# Sheet3_Power.net
KiCad netlist of a schematic drawn in Altium Designer
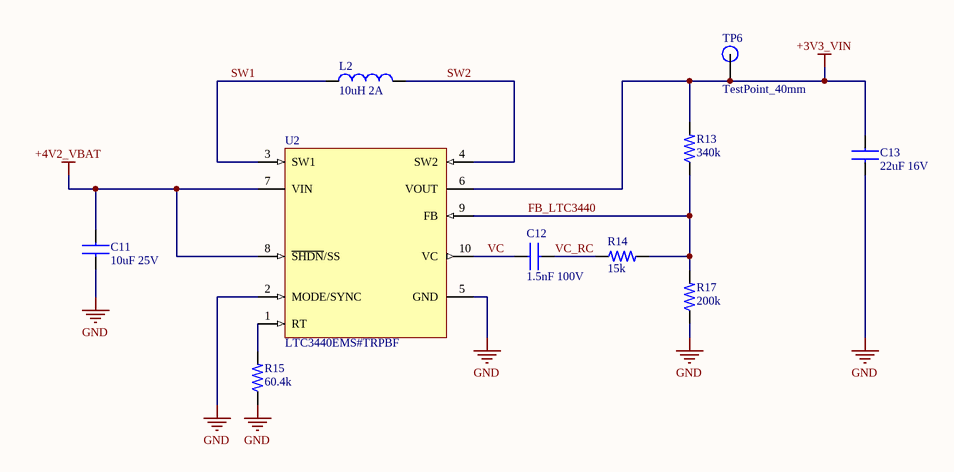
[diagram p0: Sheet3_Power.SchDoc]

(export (version "E")
  (design (tool "Eeschema 10.0.6"))
  (components
    (comp (ref "C11")
      (value "10uF 25V")
      (footprint "CAP_0805_1_4MM")
      (description "CAP CER 10UF 25V X5R 0805")
      (fields
        (field (name "MANUFACTURER") "Murata")
        (field (name "MANUFACTURER PART NUMBER") "GRM21BR61E106KA73K")
      )
      (libsource (lib "LPEDT_Parts") (part "GRM21BR61E106KA73K"))
    )
    (comp (ref "C12")
      (value "1.5nF 100V")
      (footprint "CAP_0805_1_4MM")
      (description "Cap Cer 0805 1.5NF 100V X7R 5%")
      (libsource (lib "LPEDT_Parts") (part "C0805C152J1RECAUTO"))
    )
    (comp (ref "C13")
      (value "22uF 16V")
      (footprint "CAP_0805_1_4MM")
      (description "CAP CER 22UF 16V X5R 0805")
      (fields
        (field (name "MANUFACTURER") "Samsung")
        (field (name "MANUFACTURER PART NUMBER") "CL21A226MOCLRNC")
      )
      (libsource (lib "LPEDT_Parts") (part "CL21A226MOCLRNC"))
    )
    (comp (ref "L2")
      (value "10uH 2A")
      (footprint "IND_4x4MM")
      (description "FIXED IND 10UH 2A 220 MOHM SMD")
      (fields
        (field (name "MANUFACTURER") "Laird")
        (field (name "MANUFACTURER PART NUMBER") "TYA4020100M-10")
      )
      (libsource (lib "LPEDT_Parts") (part "TYA4020100M-10"))
    )
    (comp (ref "R13")
      (value "340k")
      (footprint "RES_0603_1608X06")
      (fields
        (field (name "MANUFACTURER") "Vishay")
        (field (name "MANUFACTURER PART NUMBER") "CRCW0603340KFKEA")
        (field (name "TOLERANCE") "1%")
      )
      (libsource (lib "LPEDT_Parts") (part "CRCW0603340KFKEA"))
    )
    (comp (ref "R14")
      (value "15k")
      (footprint "RES_0603_1608X06")
      (description "SWITCH SLIDE DIP SPST 50MA 24V")
      (fields
        (field (name "MANUFACTURER") "Stackpole Electronics")
        (field (name "MANUFACTURER PART NUMBER") "RMCF0603JG15K0")
      )
      (libsource (lib "LPEDT_Parts") (part "RMCF0603JG15K0"))
    )
    (comp (ref "R15")
      (value "60.4k")
      (footprint "RES_0603_1608X06")
      (description "Res Thick Film 0603 60.4K Ohm 1% 1/10W 100ppm/C Molded SMD SMD Paper T/R")
      (fields
        (field (name "MANUFACTURER") "Stackpole Electronics")
        (field (name "MANUFACTURER PART NUMBER") "RMCF0603FT60K4")
      )
      (libsource (lib "LPEDT_Parts") (part "RMCF0603FT60K4"))
    )
    (comp (ref "R17")
      (value "200k")
      (footprint "RES_0603_1608X06")
      (fields
        (field (name "MANUFACTURER") "Vishay")
        (field (name "MANUFACTURER PART NUMBER") "CRCW0603200KFKEA")
        (field (name "TOLERANCE") "1%")
      )
      (libsource (lib "LPEDT_Parts") (part "CRCW0603200KFKEA"))
    )
    (comp (ref "TP6")
      (value "TestPoint_40mm")
      (footprint "TP_40MM")
      (libsource (lib "LPEDT_Parts") (part "TestPoint_40mm"))
    )
    (comp (ref "U2")
      (value "LTC3440EMS#TRPBF")
      (footprint "10-MSOP_3x3")
      (description "IC REG BUCK BST ADJ 0.6A 10MSOP")
      (fields (field (name "MANUFACTURER") "Analog Devices / Linear Technology"))
      (libsource (lib "LPEDT_Parts") (part "LTC3440EMS#TRPBF"))
    )
  )
  (nets
    (net (code "1") (name "+3V3_VIN") (class "Default")
      (node (ref "C13") (pin "1") (pinfunction "1_1") (pintype "passive"))
      (node (ref "R13") (pin "2") (pinfunction "2_2") (pintype "passive"))
      (node (ref "TP6") (pin "1") (pinfunction "1_1") (pintype "passive"))
      (node (ref "U2") (pin "6") (pinfunction "VOUT_6") (pintype "power_in"))
    )
    (net (code "2") (name "+4V2_VBAT") (class "Default")
      (node (ref "C11") (pin "1") (pinfunction "1_1") (pintype "passive"))
      (node (ref "U2") (pin "7") (pinfunction "VIN_7") (pintype "power_in"))
      (node (ref "U2") (pin "8") (pinfunction "~{SHDN}/SS_8") (pintype "input"))
    )
    (net (code "3") (name "/FB_LTC3440") (class "Default")
      (node (ref "R13") (pin "1") (pinfunction "1_1") (pintype "passive"))
      (node (ref "R14") (pin "2") (pinfunction "2_2") (pintype "passive"))
      (node (ref "R17") (pin "2") (pinfunction "2_2") (pintype "passive"))
      (node (ref "U2") (pin "9") (pinfunction "FB_9") (pintype "input"))
    )
    (net (code "4") (name "/SW1") (class "Default")
      (node (ref "L2") (pin "1") (pinfunction "1_1") (pintype "passive"))
      (node (ref "U2") (pin "3") (pinfunction "SW1_3") (pintype "input"))
    )
    (net (code "5") (name "/SW2") (class "Default")
      (node (ref "L2") (pin "2") (pinfunction "2_2") (pintype "passive"))
      (node (ref "U2") (pin "4") (pinfunction "SW2_4") (pintype "input"))
    )
    (net (code "6") (name "/VC") (class "Default")
      (node (ref "C12") (pin "2") (pinfunction "2_2") (pintype "passive"))
      (node (ref "U2") (pin "10") (pinfunction "VC_10") (pintype "output"))
    )
    (net (code "7") (name "/VC_RC") (class "Default")
      (node (ref "C12") (pin "1") (pinfunction "1_1") (pintype "passive"))
      (node (ref "R14") (pin "1") (pinfunction "1_1") (pintype "passive"))
    )
    (net (code "8") (name "GND") (class "Default")
      (node (ref "C11") (pin "2") (pinfunction "2_2") (pintype "passive"))
      (node (ref "C13") (pin "2") (pinfunction "2_2") (pintype "passive"))
      (node (ref "R15") (pin "1") (pinfunction "1_1") (pintype "passive"))
      (node (ref "R17") (pin "1") (pinfunction "1_1") (pintype "passive"))
      (node (ref "U2") (pin "2") (pinfunction "MODE/SYNC_2") (pintype "input"))
      (node (ref "U2") (pin "5") (pinfunction "GND_5") (pintype "power_in"))
    )
    (net (code "9") (name "Net-(U2-RT)") (class "Default")
      (node (ref "R15") (pin "2") (pinfunction "2_2") (pintype "passive"))
      (node (ref "U2") (pin "1") (pinfunction "RT_1") (pintype "input"))
    )
  )
)
